# precharge_relays.net
KiCad netlist of a schematic drawn in Altium Designer
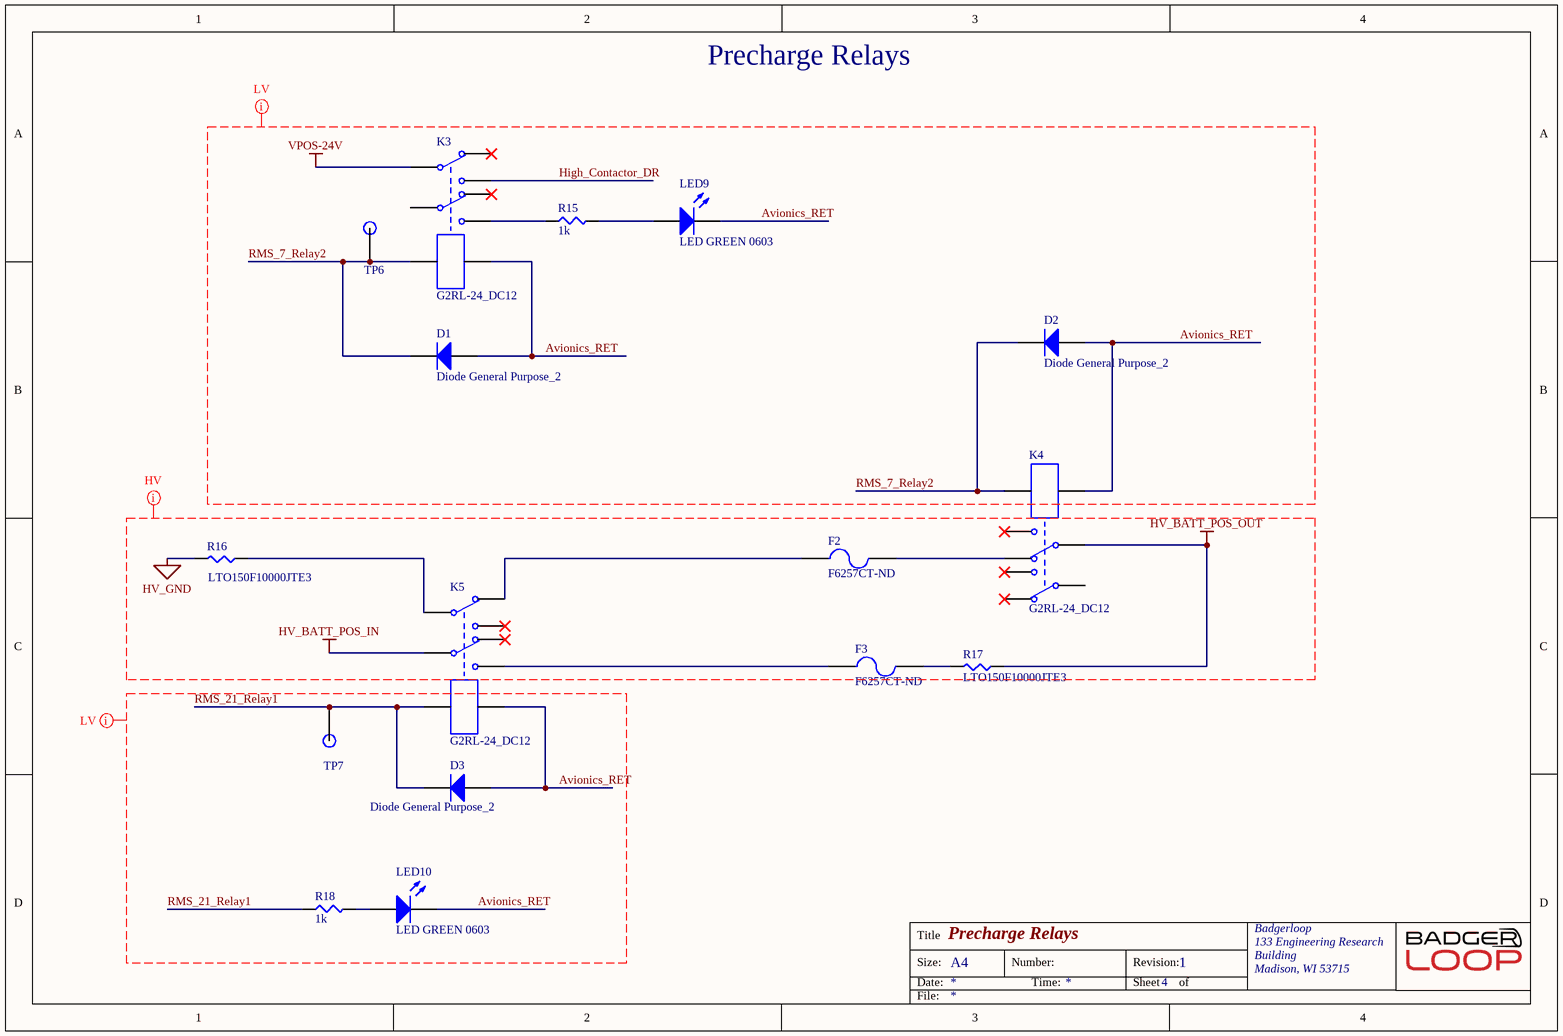
[diagram p0: precharge_relays.SchDoc]

(export (version "E")
  (design (tool "Eeschema 10.0.6"))
  (components
    (comp (ref "D1")
      (value "Diode General Purpose_2")
      (footprint "SODFL250X110-2N")
      (description "DIODE GEN PURP 20V 350MA SOD323")
      (fields (field (name "MANUFACTURER") "Diodes Incorporated"))
      (libsource (lib "misc") (part "Diode General Purpose_2"))
    )
    (comp (ref "D2")
      (value "Diode General Purpose_2")
      (footprint "SODFL250X110-2N")
      (description "DIODE GEN PURP 20V 350MA SOD323")
      (fields (field (name "MANUFACTURER") "Diodes Incorporated"))
      (libsource (lib "misc") (part "Diode General Purpose_2"))
    )
    (comp (ref "D3")
      (value "Diode General Purpose_2")
      (footprint "SODFL250X110-2N")
      (description "DIODE GEN PURP 20V 350MA SOD323")
      (fields (field (name "MANUFACTURER") "Diodes Incorporated"))
      (libsource (lib "misc") (part "Diode General Purpose_2"))
    )
    (comp (ref "F2")
      (value "F6257CT-ND")
      (footprint "FUSE BOARD MNT 500MA 350VAC/VDC")
      (description "FUSE BOARD MNT 500MA 350VAC/VDC")
      (fields (field (name "MANUFACTURER") "Littelfuse"))
      (libsource (lib "misc") (part "F6257CT-ND"))
    )
    (comp (ref "F3")
      (value "F6257CT-ND")
      (footprint "FUSE BOARD MNT 500MA 350VAC/VDC")
      (description "FUSE BOARD MNT 500MA 350VAC/VDC")
      (fields (field (name "MANUFACTURER") "Littelfuse"))
      (libsource (lib "misc") (part "F6257CT-ND"))
    )
    (comp (ref "K3")
      (value "G2RL-24_DC12")
      (footprint "G2RL")
      (description "RELAY GEN PURPOSE DPDT 8A 12V")
      (fields (field (name "MANUFACTURER") "Omron Electronics"))
      (libsource (lib "misc") (part "G2RL-24_DC12"))
    )
    (comp (ref "K4")
      (value "G2RL-24_DC12")
      (footprint "G2RL")
      (description "RELAY GEN PURPOSE DPDT 8A 12V")
      (fields (field (name "MANUFACTURER") "Omron Electronics"))
      (libsource (lib "misc") (part "G2RL-24_DC12"))
    )
    (comp (ref "K5")
      (value "G2RL-24_DC12")
      (footprint "G2RL")
      (description "RELAY GEN PURPOSE DPDT 8A 12V")
      (fields (field (name "MANUFACTURER") "Omron Electronics"))
      (libsource (lib "misc") (part "G2RL-24_DC12"))
    )
    (comp (ref "LED9")
      (value "LED GREEN 0603")
      (footprint "LED 0603 GREEN")
      (fields (field (name "MANUFACTURER") "Lite-On Inc."))
      (libsource (lib "misc") (part "LED GREEN 0603"))
    )
    (comp (ref "LED10")
      (value "LED GREEN 0603")
      (footprint "LED 0603 GREEN")
      (fields (field (name "MANUFACTURER") "Lite-On Inc."))
      (libsource (lib "misc") (part "LED GREEN 0603"))
    )
    (comp (ref "R15")
      (value "1k")
      (footprint "SMD-0805-RES")
      (description "RES SMD 1K OHM 1% 1/8W 0805")
      (fields
        (field (name "PART NUMBER") "ERJ-6ENF1001V")
        (field (name "DIGI-KEY PART NUMBER") "P1.00KCCT-ND")
      )
      (libsource (lib "resistors") (part "ERJ-6ENF1001V"))
    )
    (comp (ref "R16")
      (value "LTO150F10000JTE3")
      (footprint "TO-247-2")
      (description "RES 1K OHM 5% 150W TO247-2")
      (fields (field (name "MANUFACTURER") "Vishay Sfernice"))
      (libsource (lib "resistors") (part "LTO150F10000JTE3"))
    )
    (comp (ref "R17")
      (value "LTO150F10000JTE3")
      (footprint "TO-247-2")
      (description "RES 1K OHM 5% 150W TO247-2")
      (fields (field (name "MANUFACTURER") "Vishay Sfernice"))
      (libsource (lib "resistors") (part "LTO150F10000JTE3"))
    )
    (comp (ref "R18")
      (value "1k")
      (footprint "SMD-0805-RES")
      (description "RES SMD 1K OHM 1% 1/8W 0805")
      (fields
        (field (name "PART NUMBER") "ERJ-6ENF1001V")
        (field (name "DIGI-KEY PART NUMBER") "P1.00KCCT-ND")
      )
      (libsource (lib "resistors") (part "ERJ-6ENF1001V"))
    )
    (comp (ref "TP6")
      (value "TP")
      (footprint "Test Point")
      (description "SMD TEST POINT")
      (libsource (lib "misc") (part "TP"))
    )
    (comp (ref "TP7")
      (value "TP")
      (footprint "Test Point")
      (description "SMD TEST POINT")
      (libsource (lib "misc") (part "TP"))
    )
  )
  (nets
    (net (code "1") (name "/Avionics_RET") (class "Default")
      (node (ref "D1") (pin "1") (pinfunction "A_1") (pintype "passive"))
      (node (ref "D2") (pin "1") (pinfunction "A_1") (pintype "passive"))
      (node (ref "D3") (pin "1") (pinfunction "A_1") (pintype "passive"))
      (node (ref "K3") (pin "8") (pinfunction "8_8") (pintype "passive"))
      (node (ref "K4") (pin "1") (pinfunction "1_1") (pintype "passive"))
      (node (ref "K5") (pin "8") (pinfunction "8_8") (pintype "passive"))
      (node (ref "LED10") (pin "2") (pinfunction "K_2") (pintype "passive"))
      (node (ref "LED9") (pin "2") (pinfunction "K_2") (pintype "passive"))
    )
    (net (code "2") (name "/High_Contactor_DR") (class "Default")
      (node (ref "K3") (pin "4") (pinfunction "4_4") (pintype "passive"))
    )
    (net (code "3") (name "/RMS_7_Relay2") (class "Default")
      (node (ref "D1") (pin "2") (pinfunction "K_2") (pintype "passive"))
      (node (ref "D2") (pin "2") (pinfunction "K_2") (pintype "passive"))
      (node (ref "K3") (pin "1") (pinfunction "1_1") (pintype "passive"))
      (node (ref "K4") (pin "8") (pinfunction "8_8") (pintype "passive"))
      (node (ref "TP6") (pin "1") (pinfunction "1_1") (pintype "passive"))
    )
    (net (code "4") (name "/RMS_21_Relay1") (class "Default")
      (node (ref "D3") (pin "2") (pinfunction "K_2") (pintype "passive"))
      (node (ref "K5") (pin "1") (pinfunction "1_1") (pintype "passive"))
      (node (ref "R18") (pin "1") (pinfunction "1_1") (pintype "passive"))
      (node (ref "TP7") (pin "1") (pinfunction "1_1") (pintype "passive"))
    )
    (net (code "5") (name "HV_BATT_POS_IN") (class "Default")
      (node (ref "K5") (pin "6") (pinfunction "6_6") (pintype "passive"))
    )
    (net (code "6") (name "HV_BATT_POS_OUT") (class "Default")
      (node (ref "K4") (pin "6") (pinfunction "6_6") (pintype "passive"))
      (node (ref "R17") (pin "1") (pinfunction "1_1") (pintype "passive"))
    )
    (net (code "7") (name "HV_GND") (class "Default")
      (node (ref "R16") (pin "2") (pinfunction "2_2") (pintype "passive"))
    )
    (net (code "8") (name "Net-(F2-Pad1)") (class "Default")
      (node (ref "F2") (pin "1") (pinfunction "1_1") (pintype "passive"))
      (node (ref "K5") (pin "2") (pinfunction "2_2") (pintype "passive"))
    )
    (net (code "9") (name "Net-(F2-Pad2)") (class "Default")
      (node (ref "F2") (pin "2") (pinfunction "2_2") (pintype "passive"))
      (node (ref "K4") (pin "5") (pinfunction "5_5") (pintype "passive"))
    )
    (net (code "10") (name "Net-(F3-Pad1)") (class "Default")
      (node (ref "F3") (pin "1") (pinfunction "1_1") (pintype "passive"))
      (node (ref "K5") (pin "7") (pinfunction "7_7") (pintype "passive"))
    )
    (net (code "11") (name "Net-(F3-Pad2)") (class "Default")
      (node (ref "F3") (pin "2") (pinfunction "2_2") (pintype "passive"))
      (node (ref "R17") (pin "2") (pinfunction "2_2") (pintype "passive"))
    )
    (net (code "12") (name "Net-(K3-Pad7)") (class "Default")
      (node (ref "K3") (pin "7") (pinfunction "7_7") (pintype "passive"))
      (node (ref "R15") (pin "1") (pinfunction "1_1") (pintype "passive"))
    )
    (net (code "13") (name "Net-(K5-Pad3)") (class "Default")
      (node (ref "K5") (pin "3") (pinfunction "3_3") (pintype "passive"))
      (node (ref "R16") (pin "1") (pinfunction "1_1") (pintype "passive"))
    )
    (net (code "14") (name "Net-(LED9-A)") (class "Default")
      (node (ref "LED9") (pin "1") (pinfunction "A_1") (pintype "passive"))
      (node (ref "R15") (pin "2") (pinfunction "2_2") (pintype "passive"))
    )
    (net (code "15") (name "Net-(LED10-A)") (class "Default")
      (node (ref "LED10") (pin "1") (pinfunction "A_1") (pintype "passive"))
      (node (ref "R18") (pin "2") (pinfunction "2_2") (pintype "passive"))
    )
    (net (code "16") (name "VPOS-24V") (class "Default")
      (node (ref "K3") (pin "3") (pinfunction "3_3") (pintype "passive"))
    )
    (net (code "17") (name "unconnected-(K3-Pad2)") (class "Default")
      (node (ref "K3") (pin "2") (pinfunction "2_2") (pintype "passive+no_connect"))
    )
    (net (code "18") (name "unconnected-(K3-Pad5)") (class "Default")
      (node (ref "K3") (pin "5") (pinfunction "5_5") (pintype "passive+no_connect"))
    )
    (net (code "19") (name "unconnected-(K3-Pad6)") (class "Default")
      (node (ref "K3") (pin "6") (pinfunction "6_6") (pintype "passive"))
    )
    (net (code "20") (name "unconnected-(K4-Pad2)") (class "Default")
      (node (ref "K4") (pin "2") (pinfunction "2_2") (pintype "passive+no_connect"))
    )
    (net (code "21") (name "unconnected-(K4-Pad3)") (class "Default")
      (node (ref "K4") (pin "3") (pinfunction "3_3") (pintype "passive"))
    )
    (net (code "22") (name "unconnected-(K4-Pad4)") (class "Default")
      (node (ref "K4") (pin "4") (pinfunction "4_4") (pintype "passive+no_connect"))
    )
    (net (code "23") (name "unconnected-(K4-Pad7)") (class "Default")
      (node (ref "K4") (pin "7") (pinfunction "7_7") (pintype "passive+no_connect"))
    )
    (net (code "24") (name "unconnected-(K5-Pad4)") (class "Default")
      (node (ref "K5") (pin "4") (pinfunction "4_4") (pintype "passive+no_connect"))
    )
    (net (code "25") (name "unconnected-(K5-Pad5)") (class "Default")
      (node (ref "K5") (pin "5") (pinfunction "5_5") (pintype "passive+no_connect"))
    )
  )
)
